# CAA-NMC-OSH_panelized.net
KiCad netlist of a schematic drawn in EAGLE
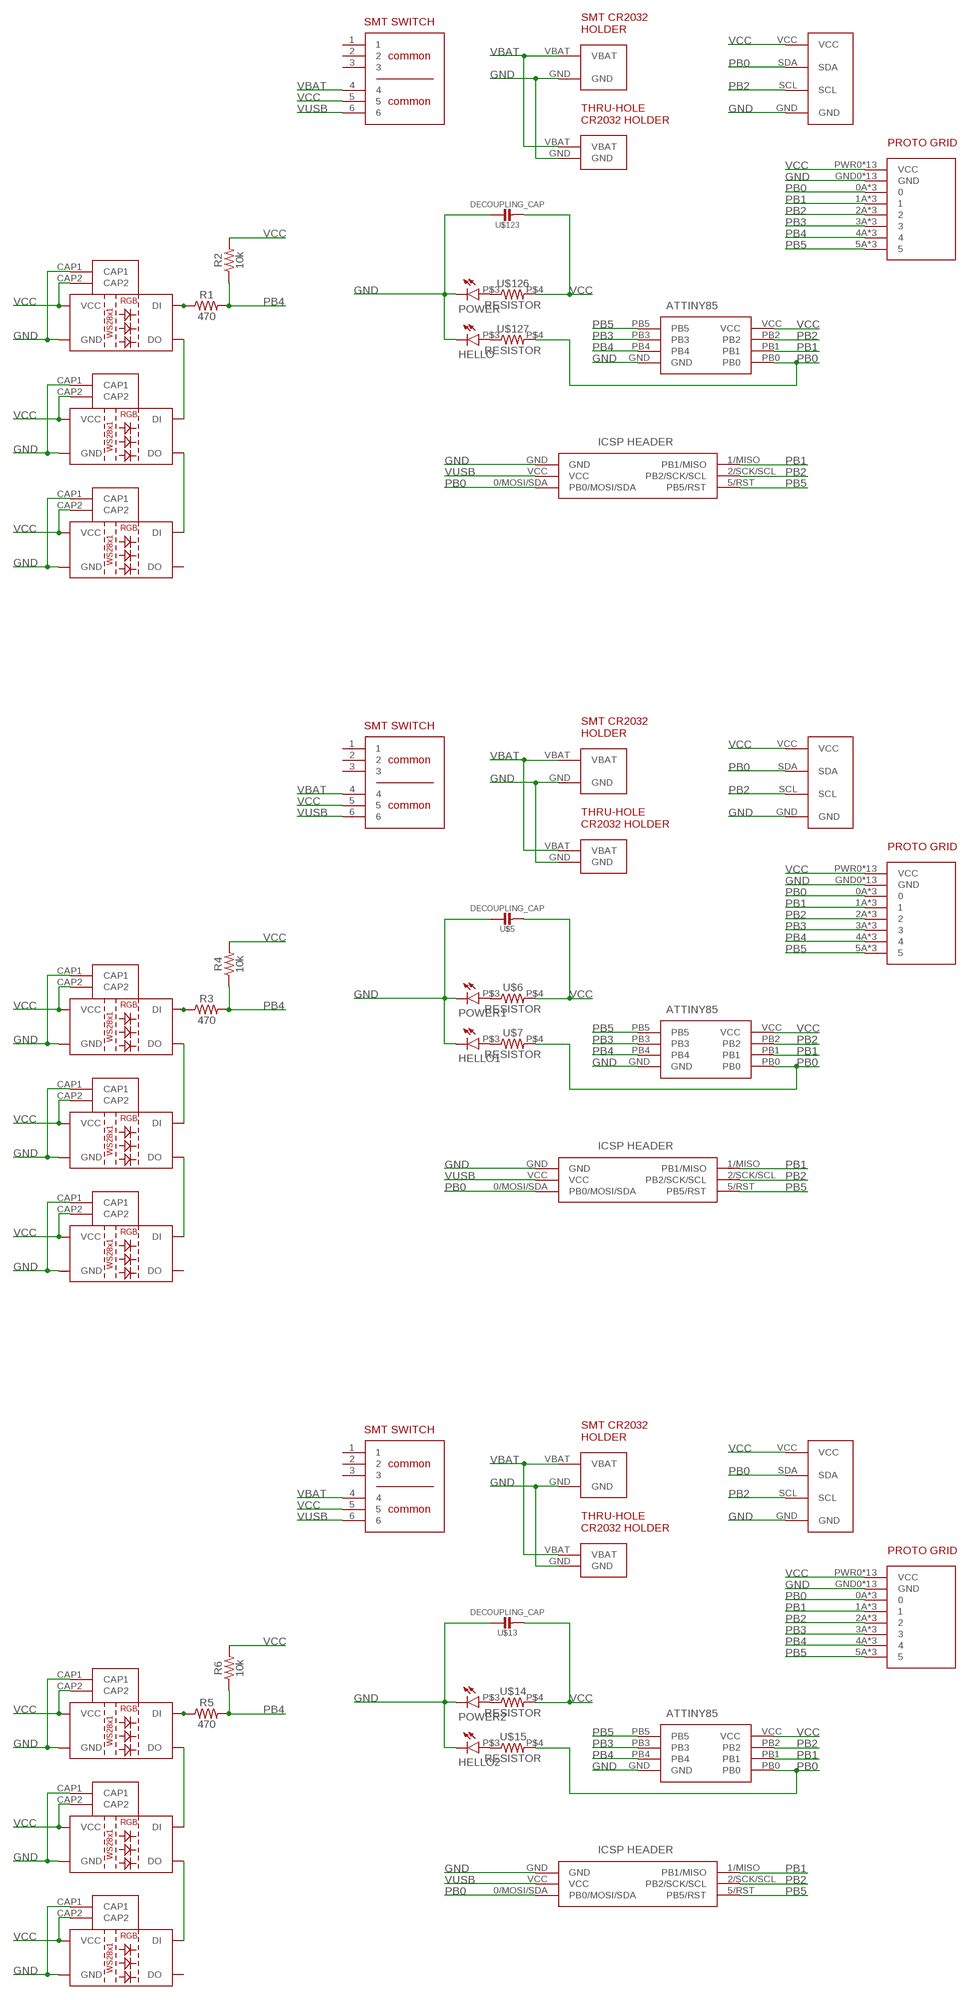
[diagram p0: schematic, sheet 1]

(export (version "E")
  (design (tool "Eeschema 10.0.6"))
  (components
    (comp (ref "D1")
      (value "WS2812B")
      (footprint "eagle-import:WS2812B")
      (libsource (lib "eagle-import") (part "WS2812B"))
    )
    (comp (ref "D2")
      (value "WS2812B")
      (footprint "eagle-import:WS2812B")
      (libsource (lib "eagle-import") (part "WS2812B"))
    )
    (comp (ref "D3")
      (value "WS2812B")
      (footprint "eagle-import:WS2812B")
      (libsource (lib "eagle-import") (part "WS2812B"))
    )
    (comp (ref "D4")
      (value "WS2812B")
      (footprint "eagle-import:WS2812B")
      (libsource (lib "eagle-import") (part "WS2812B"))
    )
    (comp (ref "D5")
      (value "WS2812B")
      (footprint "eagle-import:WS2812B")
      (libsource (lib "eagle-import") (part "WS2812B"))
    )
    (comp (ref "D6")
      (value "WS2812B")
      (footprint "eagle-import:WS2812B")
      (libsource (lib "eagle-import") (part "WS2812B"))
    )
    (comp (ref "D7")
      (value "WS2812B")
      (footprint "eagle-import:WS2812B")
      (libsource (lib "eagle-import") (part "WS2812B"))
    )
    (comp (ref "D8")
      (value "WS2812B")
      (footprint "eagle-import:WS2812B")
      (libsource (lib "eagle-import") (part "WS2812B"))
    )
    (comp (ref "D9")
      (value "WS2812B")
      (footprint "eagle-import:WS2812B")
      (libsource (lib "eagle-import") (part "WS2812B"))
    )
    (comp (ref "HELLO")
      (value "LED3MM")
      (footprint "eagle-import:LED3MM")
      (libsource (lib "eagle-import") (part "LED3MM"))
    )
    (comp (ref "HELLO1")
      (value "LED3MM")
      (footprint "eagle-import:LED3MM")
      (libsource (lib "eagle-import") (part "LED3MM"))
    )
    (comp (ref "HELLO2")
      (value "LED3MM")
      (footprint "eagle-import:LED3MM")
      (libsource (lib "eagle-import") (part "LED3MM"))
    )
    (comp (ref "IC1")
      (value "ATTINY85-20SU")
      (footprint "eagle-import:SOT127P798X216-8N")
      (fields (field (name "RS_PART_NUMBER") "1331674"))
      (libsource (lib "eagle-import") (part "ATTINY85-20SU"))
    )
    (comp (ref "IC2")
      (value "ATTINY85-20SU")
      (footprint "eagle-import:SOT127P798X216-8N")
      (fields (field (name "RS_PART_NUMBER") "1331674"))
      (libsource (lib "eagle-import") (part "ATTINY85-20SU"))
    )
    (comp (ref "IC3")
      (value "ATTINY85-20SU")
      (footprint "eagle-import:SOT127P798X216-8N")
      (fields (field (name "RS_PART_NUMBER") "1331674"))
      (libsource (lib "eagle-import") (part "ATTINY85-20SU"))
    )
    (comp (ref "J1")
      (value "M20-9980346")
      (footprint "eagle-import:HDRV6W64P254_2X3_762X508X868P")
      (fields (field (name "RS_PART_NUMBER") "7457046P"))
      (libsource (lib "eagle-import") (part "M20-9980346"))
    )
    (comp (ref "J2")
      (value "M20-9980346")
      (footprint "eagle-import:HDRV6W64P254_2X3_762X508X868P")
      (fields (field (name "RS_PART_NUMBER") "7457046P"))
      (libsource (lib "eagle-import") (part "M20-9980346"))
    )
    (comp (ref "J3")
      (value "M20-9980346")
      (footprint "eagle-import:HDRV6W64P254_2X3_762X508X868P")
      (fields (field (name "RS_PART_NUMBER") "7457046P"))
      (libsource (lib "eagle-import") (part "M20-9980346"))
    )
    (comp (ref "POWER")
      (value "LED3MM")
      (footprint "eagle-import:LED3MM")
      (libsource (lib "eagle-import") (part "LED3MM"))
    )
    (comp (ref "POWER1")
      (value "LED3MM")
      (footprint "eagle-import:LED3MM")
      (libsource (lib "eagle-import") (part "LED3MM"))
    )
    (comp (ref "POWER2")
      (value "LED3MM")
      (footprint "eagle-import:LED3MM")
      (libsource (lib "eagle-import") (part "LED3MM"))
    )
    (comp (ref "R1")
      (value "470")
      (footprint "eagle-import:0603")
      (libsource (lib "eagle-import") (part "470OHM-0603-1/10W-1%"))
    )
    (comp (ref "R2")
      (value "10k")
      (footprint "eagle-import:0603")
      (libsource (lib "eagle-import") (part "10KOHM-0603-1/10W-1%"))
    )
    (comp (ref "R3")
      (value "470")
      (footprint "eagle-import:0603")
      (libsource (lib "eagle-import") (part "470OHM-0603-1/10W-1%"))
    )
    (comp (ref "R4")
      (value "10k")
      (footprint "eagle-import:0603")
      (libsource (lib "eagle-import") (part "10KOHM-0603-1/10W-1%"))
    )
    (comp (ref "R5")
      (value "470")
      (footprint "eagle-import:0603")
      (libsource (lib "eagle-import") (part "470OHM-0603-1/10W-1%"))
    )
    (comp (ref "R6")
      (value "10k")
      (footprint "eagle-import:0603")
      (libsource (lib "eagle-import") (part "10KOHM-0603-1/10W-1%"))
    )
    (comp (ref "U$1")
      (value "PROTO")
      (footprint "eagle-import:PROTO")
      (libsource (lib "eagle-import") (part "PROTO"))
    )
    (comp (ref "U$2")
      (value "SMT-BATTERY-HOLDER")
      (footprint "eagle-import:SMT-CR-HOLDER")
      (libsource (lib "eagle-import") (part "SMT-BATTERY-HOLDER"))
    )
    (comp (ref "U$3")
      (value "THRU-CR-HOLDER")
      (footprint "eagle-import:THRU-CR-HOLDER")
      (libsource (lib "eagle-import") (part "THRU-CR-HOLDER"))
    )
    (comp (ref "U$4")
      (value "I2C-PADS")
      (footprint "eagle-import:I2C-PADS")
      (libsource (lib "eagle-import") (part "I2C-PADS"))
    )
    (comp (ref "U$5")
      (value "DECOUPLING_CAP")
      (footprint "eagle-import:DECOUPLING_CAP")
      (libsource (lib "eagle-import") (part "DECOUPLING_CAP"))
    )
    (comp (ref "U$6")
      (value "RESISTOR")
      (footprint "eagle-import:AXIAL-0.3")
      (libsource (lib "eagle-import") (part "RESISTOR"))
    )
    (comp (ref "U$7")
      (value "RESISTOR")
      (footprint "eagle-import:AXIAL-0.3")
      (libsource (lib "eagle-import") (part "RESISTOR"))
    )
    (comp (ref "U$8")
      (value "SMT-SWITCH")
      (footprint "eagle-import:SMT-SWITCH")
      (libsource (lib "eagle-import") (part "SMT-SWITCH"))
    )
    (comp (ref "U$9")
      (value "PROTO")
      (footprint "eagle-import:PROTO")
      (libsource (lib "eagle-import") (part "PROTO"))
    )
    (comp (ref "U$10")
      (value "SMT-BATTERY-HOLDER")
      (footprint "eagle-import:SMT-CR-HOLDER")
      (libsource (lib "eagle-import") (part "SMT-BATTERY-HOLDER"))
    )
    (comp (ref "U$11")
      (value "THRU-CR-HOLDER")
      (footprint "eagle-import:THRU-CR-HOLDER")
      (libsource (lib "eagle-import") (part "THRU-CR-HOLDER"))
    )
    (comp (ref "U$12")
      (value "I2C-PADS")
      (footprint "eagle-import:I2C-PADS")
      (libsource (lib "eagle-import") (part "I2C-PADS"))
    )
    (comp (ref "U$13")
      (value "DECOUPLING_CAP")
      (footprint "eagle-import:DECOUPLING_CAP")
      (libsource (lib "eagle-import") (part "DECOUPLING_CAP"))
    )
    (comp (ref "U$14")
      (value "RESISTOR")
      (footprint "eagle-import:AXIAL-0.3")
      (libsource (lib "eagle-import") (part "RESISTOR"))
    )
    (comp (ref "U$15")
      (value "RESISTOR")
      (footprint "eagle-import:AXIAL-0.3")
      (libsource (lib "eagle-import") (part "RESISTOR"))
    )
    (comp (ref "U$16")
      (value "SMT-SWITCH")
      (footprint "eagle-import:SMT-SWITCH")
      (libsource (lib "eagle-import") (part "SMT-SWITCH"))
    )
    (comp (ref "U$17")
      (value "PROTO")
      (footprint "eagle-import:PROTO")
      (libsource (lib "eagle-import") (part "PROTO"))
    )
    (comp (ref "U$18")
      (value "SMT-BATTERY-HOLDER")
      (footprint "eagle-import:SMT-CR-HOLDER")
      (libsource (lib "eagle-import") (part "SMT-BATTERY-HOLDER"))
    )
    (comp (ref "U$19")
      (value "THRU-CR-HOLDER")
      (footprint "eagle-import:THRU-CR-HOLDER")
      (libsource (lib "eagle-import") (part "THRU-CR-HOLDER"))
    )
    (comp (ref "U$20")
      (value "I2C-PADS")
      (footprint "eagle-import:I2C-PADS")
      (libsource (lib "eagle-import") (part "I2C-PADS"))
    )
    (comp (ref "U$123")
      (value "DECOUPLING_CAP")
      (footprint "eagle-import:DECOUPLING_CAP")
      (libsource (lib "eagle-import") (part "DECOUPLING_CAP"))
    )
    (comp (ref "U$126")
      (value "RESISTOR")
      (footprint "eagle-import:AXIAL-0.3")
      (libsource (lib "eagle-import") (part "RESISTOR"))
    )
    (comp (ref "U$127")
      (value "RESISTOR")
      (footprint "eagle-import:AXIAL-0.3")
      (libsource (lib "eagle-import") (part "RESISTOR"))
    )
    (comp (ref "U$145")
      (value "SMT-SWITCH")
      (footprint "eagle-import:SMT-SWITCH")
      (libsource (lib "eagle-import") (part "SMT-SWITCH"))
    )
  )
  (nets
    (net (code "1") (name "/GND") (class "Default")
      (node (ref "D1") (pin "CAP1") (pinfunction "CAP1_CAP1") (pintype "bidirectional"))
      (node (ref "D1") (pin "GND") (pinfunction "GND_GND") (pintype "bidirectional"))
      (node (ref "D2") (pin "CAP1") (pinfunction "CAP1_CAP1") (pintype "bidirectional"))
      (node (ref "D2") (pin "GND") (pinfunction "GND_GND") (pintype "bidirectional"))
      (node (ref "D3") (pin "CAP1") (pinfunction "CAP1_CAP1") (pintype "bidirectional"))
      (node (ref "D3") (pin "GND") (pinfunction "GND_GND") (pintype "bidirectional"))
      (node (ref "D4") (pin "CAP1") (pinfunction "CAP1_CAP1") (pintype "bidirectional"))
      (node (ref "D4") (pin "GND") (pinfunction "GND_GND") (pintype "bidirectional"))
      (node (ref "D5") (pin "CAP1") (pinfunction "CAP1_CAP1") (pintype "bidirectional"))
      (node (ref "D5") (pin "GND") (pinfunction "GND_GND") (pintype "bidirectional"))
      (node (ref "D6") (pin "CAP1") (pinfunction "CAP1_CAP1") (pintype "bidirectional"))
      (node (ref "D6") (pin "GND") (pinfunction "GND_GND") (pintype "bidirectional"))
      (node (ref "D7") (pin "CAP1") (pinfunction "CAP1_CAP1") (pintype "bidirectional"))
      (node (ref "D7") (pin "GND") (pinfunction "GND_GND") (pintype "bidirectional"))
      (node (ref "D8") (pin "CAP1") (pinfunction "CAP1_CAP1") (pintype "bidirectional"))
      (node (ref "D8") (pin "GND") (pinfunction "GND_GND") (pintype "bidirectional"))
      (node (ref "D9") (pin "CAP1") (pinfunction "CAP1_CAP1") (pintype "bidirectional"))
      (node (ref "D9") (pin "GND") (pinfunction "GND_GND") (pintype "bidirectional"))
      (node (ref "HELLO") (pin "NEG") (pinfunction "NEG_NEG") (pintype "passive"))
      (node (ref "HELLO1") (pin "NEG") (pinfunction "NEG_NEG") (pintype "passive"))
      (node (ref "HELLO2") (pin "NEG") (pinfunction "NEG_NEG") (pintype "passive"))
      (node (ref "IC1") (pin "GND") (pinfunction "GND_GND") (pintype "bidirectional"))
      (node (ref "IC2") (pin "GND") (pinfunction "GND_GND") (pintype "bidirectional"))
      (node (ref "IC3") (pin "GND") (pinfunction "GND_GND") (pintype "bidirectional"))
      (node (ref "J1") (pin "GND") (pinfunction "GND_GND") (pintype "bidirectional"))
      (node (ref "J2") (pin "GND") (pinfunction "GND_GND") (pintype "bidirectional"))
      (node (ref "J3") (pin "GND") (pinfunction "GND_GND") (pintype "bidirectional"))
      (node (ref "POWER") (pin "NEG") (pinfunction "NEG_NEG") (pintype "passive"))
      (node (ref "POWER1") (pin "NEG") (pinfunction "NEG_NEG") (pintype "passive"))
      (node (ref "POWER2") (pin "NEG") (pinfunction "NEG_NEG") (pintype "passive"))
      (node (ref "U$1") (pin "GND0") (pinfunction "GND_GND0") (pintype "bidirectional"))
      (node (ref "U$1") (pin "GND1") (pinfunction "GND_GND1") (pintype "bidirectional"))
      (node (ref "U$1") (pin "GND10") (pinfunction "GND_GND10") (pintype "bidirectional"))
      (node (ref "U$1") (pin "GND11") (pinfunction "GND_GND11") (pintype "bidirectional"))
      (node (ref "U$1") (pin "GND12") (pinfunction "GND_GND12") (pintype "bidirectional"))
      (node (ref "U$1") (pin "GND2") (pinfunction "GND_GND2") (pintype "bidirectional"))
      (node (ref "U$1") (pin "GND3") (pinfunction "GND_GND3") (pintype "bidirectional"))
      (node (ref "U$1") (pin "GND4") (pinfunction "GND_GND4") (pintype "bidirectional"))
      (node (ref "U$1") (pin "GND5") (pinfunction "GND_GND5") (pintype "bidirectional"))
      (node (ref "U$1") (pin "GND6") (pinfunction "GND_GND6") (pintype "bidirectional"))
      (node (ref "U$1") (pin "GND7") (pinfunction "GND_GND7") (pintype "bidirectional"))
      (node (ref "U$1") (pin "GND8") (pinfunction "GND_GND8") (pintype "bidirectional"))
      (node (ref "U$1") (pin "GND9") (pinfunction "GND_GND9") (pintype "bidirectional"))
      (node (ref "U$10") (pin "GND") (pinfunction "GND_GND") (pintype "bidirectional"))
      (node (ref "U$11") (pin "GND") (pinfunction "GND_GND") (pintype "bidirectional"))
      (node (ref "U$12") (pin "GND") (pinfunction "GND_GND") (pintype "bidirectional"))
      (node (ref "U$123") (pin "P$1") (pinfunction "1_P$1") (pintype "passive"))
      (node (ref "U$13") (pin "P$1") (pinfunction "1_P$1") (pintype "passive"))
      (node (ref "U$17") (pin "GND0") (pinfunction "GND_GND0") (pintype "bidirectional"))
      (node (ref "U$17") (pin "GND1") (pinfunction "GND_GND1") (pintype "bidirectional"))
      (node (ref "U$17") (pin "GND10") (pinfunction "GND_GND10") (pintype "bidirectional"))
      (node (ref "U$17") (pin "GND11") (pinfunction "GND_GND11") (pintype "bidirectional"))
      (node (ref "U$17") (pin "GND12") (pinfunction "GND_GND12") (pintype "bidirectional"))
      (node (ref "U$17") (pin "GND2") (pinfunction "GND_GND2") (pintype "bidirectional"))
      (node (ref "U$17") (pin "GND3") (pinfunction "GND_GND3") (pintype "bidirectional"))
      (node (ref "U$17") (pin "GND4") (pinfunction "GND_GND4") (pintype "bidirectional"))
      (node (ref "U$17") (pin "GND5") (pinfunction "GND_GND5") (pintype "bidirectional"))
      (node (ref "U$17") (pin "GND6") (pinfunction "GND_GND6") (pintype "bidirectional"))
      (node (ref "U$17") (pin "GND7") (pinfunction "GND_GND7") (pintype "bidirectional"))
      (node (ref "U$17") (pin "GND8") (pinfunction "GND_GND8") (pintype "bidirectional"))
      (node (ref "U$17") (pin "GND9") (pinfunction "GND_GND9") (pintype "bidirectional"))
      (node (ref "U$18") (pin "GND") (pinfunction "GND_GND") (pintype "bidirectional"))
      (node (ref "U$19") (pin "GND") (pinfunction "GND_GND") (pintype "bidirectional"))
      (node (ref "U$2") (pin "GND") (pinfunction "GND_GND") (pintype "bidirectional"))
      (node (ref "U$20") (pin "GND") (pinfunction "GND_GND") (pintype "bidirectional"))
      (node (ref "U$3") (pin "GND") (pinfunction "GND_GND") (pintype "bidirectional"))
      (node (ref "U$4") (pin "GND") (pinfunction "GND_GND") (pintype "bidirectional"))
      (node (ref "U$5") (pin "P$1") (pinfunction "1_P$1") (pintype "passive"))
      (node (ref "U$9") (pin "GND0") (pinfunction "GND_GND0") (pintype "bidirectional"))
      (node (ref "U$9") (pin "GND1") (pinfunction "GND_GND1") (pintype "bidirectional"))
      (node (ref "U$9") (pin "GND10") (pinfunction "GND_GND10") (pintype "bidirectional"))
      (node (ref "U$9") (pin "GND11") (pinfunction "GND_GND11") (pintype "bidirectional"))
      (node (ref "U$9") (pin "GND12") (pinfunction "GND_GND12") (pintype "bidirectional"))
      (node (ref "U$9") (pin "GND2") (pinfunction "GND_GND2") (pintype "bidirectional"))
      (node (ref "U$9") (pin "GND3") (pinfunction "GND_GND3") (pintype "bidirectional"))
      (node (ref "U$9") (pin "GND4") (pinfunction "GND_GND4") (pintype "bidirectional"))
      (node (ref "U$9") (pin "GND5") (pinfunction "GND_GND5") (pintype "bidirectional"))
      (node (ref "U$9") (pin "GND6") (pinfunction "GND_GND6") (pintype "bidirectional"))
      (node (ref "U$9") (pin "GND7") (pinfunction "GND_GND7") (pintype "bidirectional"))
      (node (ref "U$9") (pin "GND8") (pinfunction "GND_GND8") (pintype "bidirectional"))
      (node (ref "U$9") (pin "GND9") (pinfunction "GND_GND9") (pintype "bidirectional"))
    )
    (net (code "2") (name "/PB0") (class "Default")
      (node (ref "IC1") (pin "PB0") (pinfunction "PB0_PB0") (pintype "bidirectional"))
      (node (ref "IC2") (pin "PB0") (pinfunction "PB0_PB0") (pintype "bidirectional"))
      (node (ref "IC3") (pin "PB0") (pinfunction "PB0_PB0") (pintype "bidirectional"))
      (node (ref "J1") (pin "0/MOSI/SDA") (pinfunction "PB0/MOSI/SDA_0/MOSI/SDA") (pintype "bidirectional"))
      (node (ref "J2") (pin "0/MOSI/SDA") (pinfunction "PB0/MOSI/SDA_0/MOSI/SDA") (pintype "bidirectional"))
      (node (ref "J3") (pin "0/MOSI/SDA") (pinfunction "PB0/MOSI/SDA_0/MOSI/SDA") (pintype "bidirectional"))
      (node (ref "U$1") (pin "0A") (pinfunction "0_0A") (pintype "bidirectional"))
      (node (ref "U$1") (pin "0B") (pinfunction "0_0B") (pintype "bidirectional"))
      (node (ref "U$1") (pin "0C") (pinfunction "0_0C") (pintype "bidirectional"))
      (node (ref "U$12") (pin "SDA") (pinfunction "SDA_SDA") (pintype "bidirectional"))
      (node (ref "U$127") (pin "P$4") (pinfunction "2_P$4") (pintype "passive"))
      (node (ref "U$15") (pin "P$4") (pinfunction "2_P$4") (pintype "passive"))
      (node (ref "U$17") (pin "0A") (pinfunction "0_0A") (pintype "bidirectional"))
      (node (ref "U$17") (pin "0B") (pinfunction "0_0B") (pintype "bidirectional"))
      (node (ref "U$17") (pin "0C") (pinfunction "0_0C") (pintype "bidirectional"))
      (node (ref "U$20") (pin "SDA") (pinfunction "SDA_SDA") (pintype "bidirectional"))
      (node (ref "U$4") (pin "SDA") (pinfunction "SDA_SDA") (pintype "bidirectional"))
      (node (ref "U$7") (pin "P$4") (pinfunction "2_P$4") (pintype "passive"))
      (node (ref "U$9") (pin "0A") (pinfunction "0_0A") (pintype "bidirectional"))
      (node (ref "U$9") (pin "0B") (pinfunction "0_0B") (pintype "bidirectional"))
      (node (ref "U$9") (pin "0C") (pinfunction "0_0C") (pintype "bidirectional"))
    )
    (net (code "3") (name "/PB1") (class "Default")
      (node (ref "IC1") (pin "PB1") (pinfunction "PB1_PB1") (pintype "bidirectional"))
      (node (ref "IC2") (pin "PB1") (pinfunction "PB1_PB1") (pintype "bidirectional"))
      (node (ref "IC3") (pin "PB1") (pinfunction "PB1_PB1") (pintype "bidirectional"))
      (node (ref "J1") (pin "1/MISO") (pinfunction "PB1/MISO_1/MISO") (pintype "bidirectional"))
      (node (ref "J2") (pin "1/MISO") (pinfunction "PB1/MISO_1/MISO") (pintype "bidirectional"))
      (node (ref "J3") (pin "1/MISO") (pinfunction "PB1/MISO_1/MISO") (pintype "bidirectional"))
      (node (ref "U$1") (pin "1A") (pinfunction "1_1A") (pintype "bidirectional"))
      (node (ref "U$1") (pin "1B") (pinfunction "1_1B") (pintype "bidirectional"))
      (node (ref "U$1") (pin "1C") (pinfunction "1_1C") (pintype "bidirectional"))
      (node (ref "U$17") (pin "1A") (pinfunction "1_1A") (pintype "bidirectional"))
      (node (ref "U$17") (pin "1B") (pinfunction "1_1B") (pintype "bidirectional"))
      (node (ref "U$17") (pin "1C") (pinfunction "1_1C") (pintype "bidirectional"))
      (node (ref "U$9") (pin "1A") (pinfunction "1_1A") (pintype "bidirectional"))
      (node (ref "U$9") (pin "1B") (pinfunction "1_1B") (pintype "bidirectional"))
      (node (ref "U$9") (pin "1C") (pinfunction "1_1C") (pintype "bidirectional"))
    )
    (net (code "4") (name "/PB2") (class "Default")
      (node (ref "IC1") (pin "PB2") (pinfunction "PB2_PB2") (pintype "bidirectional"))
      (node (ref "IC2") (pin "PB2") (pinfunction "PB2_PB2") (pintype "bidirectional"))
      (node (ref "IC3") (pin "PB2") (pinfunction "PB2_PB2") (pintype "bidirectional"))
      (node (ref "J1") (pin "2/SCK/SCL") (pinfunction "PB2/SCK/SCL_2/SCK/SCL") (pintype "bidirectional"))
      (node (ref "J2") (pin "2/SCK/SCL") (pinfunction "PB2/SCK/SCL_2/SCK/SCL") (pintype "bidirectional"))
      (node (ref "J3") (pin "2/SCK/SCL") (pinfunction "PB2/SCK/SCL_2/SCK/SCL") (pintype "bidirectional"))
      (node (ref "U$1") (pin "2A") (pinfunction "2_2A") (pintype "bidirectional"))
      (node (ref "U$1") (pin "2B") (pinfunction "2_2B") (pintype "bidirectional"))
      (node (ref "U$1") (pin "2C") (pinfunction "2_2C") (pintype "bidirectional"))
      (node (ref "U$12") (pin "SCL") (pinfunction "SCL_SCL") (pintype "bidirectional"))
      (node (ref "U$17") (pin "2A") (pinfunction "2_2A") (pintype "bidirectional"))
      (node (ref "U$17") (pin "2B") (pinfunction "2_2B") (pintype "bidirectional"))
      (node (ref "U$17") (pin "2C") (pinfunction "2_2C") (pintype "bidirectional"))
      (node (ref "U$20") (pin "SCL") (pinfunction "SCL_SCL") (pintype "bidirectional"))
      (node (ref "U$4") (pin "SCL") (pinfunction "SCL_SCL") (pintype "bidirectional"))
      (node (ref "U$9") (pin "2A") (pinfunction "2_2A") (pintype "bidirectional"))
      (node (ref "U$9") (pin "2B") (pinfunction "2_2B") (pintype "bidirectional"))
      (node (ref "U$9") (pin "2C") (pinfunction "2_2C") (pintype "bidirectional"))
    )
    (net (code "5") (name "/PB3") (class "Default")
      (node (ref "IC1") (pin "PB3") (pinfunction "PB3_PB3") (pintype "bidirectional"))
      (node (ref "IC2") (pin "PB3") (pinfunction "PB3_PB3") (pintype "bidirectional"))
      (node (ref "IC3") (pin "PB3") (pinfunction "PB3_PB3") (pintype "bidirectional"))
      (node (ref "U$1") (pin "3A") (pinfunction "3_3A") (pintype "bidirectional"))
      (node (ref "U$1") (pin "3B") (pinfunction "3_3B") (pintype "bidirectional"))
      (node (ref "U$1") (pin "3C") (pinfunction "3_3C") (pintype "bidirectional"))
      (node (ref "U$17") (pin "3A") (pinfunction "3_3A") (pintype "bidirectional"))
      (node (ref "U$17") (pin "3B") (pinfunction "3_3B") (pintype "bidirectional"))
      (node (ref "U$17") (pin "3C") (pinfunction "3_3C") (pintype "bidirectional"))
      (node (ref "U$9") (pin "3A") (pinfunction "3_3A") (pintype "bidirectional"))
      (node (ref "U$9") (pin "3B") (pinfunction "3_3B") (pintype "bidirectional"))
      (node (ref "U$9") (pin "3C") (pinfunction "3_3C") (pintype "bidirectional"))
    )
    (net (code "6") (name "/PB4") (class "Default")
      (node (ref "IC1") (pin "PB4") (pinfunction "PB4_PB4") (pintype "bidirectional"))
      (node (ref "IC2") (pin "PB4") (pinfunction "PB4_PB4") (pintype "bidirectional"))
      (node (ref "IC3") (pin "PB4") (pinfunction "PB4_PB4") (pintype "bidirectional"))
      (node (ref "R1") (pin "2") (pinfunction "2_2") (pintype "passive"))
      (node (ref "R2") (pin "1") (pinfunction "1_1") (pintype "passive"))
      (node (ref "R3") (pin "2") (pinfunction "2_2") (pintype "passive"))
      (node (ref "R4") (pin "1") (pinfunction "1_1") (pintype "passive"))
      (node (ref "R5") (pin "2") (pinfunction "2_2") (pintype "passive"))
      (node (ref "R6") (pin "1") (pinfunction "1_1") (pintype "passive"))
      (node (ref "U$1") (pin "4A") (pinfunction "4_4A") (pintype "bidirectional"))
      (node (ref "U$1") (pin "4B") (pinfunction "4_4B") (pintype "bidirectional"))
      (node (ref "U$1") (pin "4C") (pinfunction "4_4C") (pintype "bidirectional"))
      (node (ref "U$17") (pin "4A") (pinfunction "4_4A") (pintype "bidirectional"))
      (node (ref "U$17") (pin "4B") (pinfunction "4_4B") (pintype "bidirectional"))
      (node (ref "U$17") (pin "4C") (pinfunction "4_4C") (pintype "bidirectional"))
      (node (ref "U$9") (pin "4A") (pinfunction "4_4A") (pintype "bidirectional"))
      (node (ref "U$9") (pin "4B") (pinfunction "4_4B") (pintype "bidirectional"))
      (node (ref "U$9") (pin "4C") (pinfunction "4_4C") (pintype "bidirectional"))
    )
    (net (code "7") (name "/PB5") (class "Default")
      (node (ref "IC1") (pin "PB5") (pinfunction "PB5_PB5") (pintype "bidirectional"))
      (node (ref "IC2") (pin "PB5") (pinfunction "PB5_PB5") (pintype "bidirectional"))
      (node (ref "IC3") (pin "PB5") (pinfunction "PB5_PB5") (pintype "bidirectional"))
      (node (ref "J1") (pin "5/RST") (pinfunction "PB5/RST_5/RST") (pintype "bidirectional"))
      (node (ref "J2") (pin "5/RST") (pinfunction "PB5/RST_5/RST") (pintype "bidirectional"))
      (node (ref "J3") (pin "5/RST") (pinfunction "PB5/RST_5/RST") (pintype "bidirectional"))
      (node (ref "U$1") (pin "5A") (pinfunction "5_5A") (pintype "bidirectional"))
      (node (ref "U$1") (pin "5B") (pinfunction "5_5B") (pintype "bidirectional"))
      (node (ref "U$1") (pin "5C") (pinfunction "5_5C") (pintype "bidirectional"))
      (node (ref "U$17") (pin "5A") (pinfunction "5_5A") (pintype "bidirectional"))
      (node (ref "U$17") (pin "5B") (pinfunction "5_5B") (pintype "bidirectional"))
      (node (ref "U$17") (pin "5C") (pinfunction "5_5C") (pintype "bidirectional"))
      (node (ref "U$9") (pin "5A") (pinfunction "5_5A") (pintype "bidirectional"))
      (node (ref "U$9") (pin "5B") (pinfunction "5_5B") (pintype "bidirectional"))
      (node (ref "U$9") (pin "5C") (pinfunction "5_5C") (pintype "bidirectional"))
    )
    (net (code "8") (name "/VBAT") (class "Default")
      (node (ref "U$10") (pin "VBAT") (pinfunction "VBAT_VBAT") (pintype "bidirectional"))
      (node (ref "U$11") (pin "VBAT") (pinfunction "VBAT_VBAT") (pintype "bidirectional"))
      (node (ref "U$145") (pin "4") (pinfunction "4_4") (pintype "bidirectional"))
      (node (ref "U$16") (pin "4") (pinfunction "4_4") (pintype "bidirectional"))
      (node (ref "U$18") (pin "VBAT") (pinfunction "VBAT_VBAT") (pintype "bidirectional"))
      (node (ref "U$19") (pin "VBAT") (pinfunction "VBAT_VBAT") (pintype "bidirectional"))
      (node (ref "U$2") (pin "VBAT") (pinfunction "VBAT_VBAT") (pintype "bidirectional"))
      (node (ref "U$3") (pin "VBAT") (pinfunction "VBAT_VBAT") (pintype "bidirectional"))
      (node (ref "U$8") (pin "4") (pinfunction "4_4") (pintype "bidirectional"))
    )
    (net (code "9") (name "/VCC") (class "Default")
      (node (ref "D1") (pin "CAP2") (pinfunction "CAP2_CAP2") (pintype "bidirectional"))
      (node (ref "D1") (pin "VCC") (pinfunction "VCC_VCC") (pintype "bidirectional"))
      (node (ref "D2") (pin "CAP2") (pinfunction "CAP2_CAP2") (pintype "bidirectional"))
      (node (ref "D2") (pin "VCC") (pinfunction "VCC_VCC") (pintype "bidirectional"))
      (node (ref "D3") (pin "CAP2") (pinfunction "CAP2_CAP2") (pintype "bidirectional"))
      (node (ref "D3") (pin "VCC") (pinfunction "VCC_VCC") (pintype "bidirectional"))
      (node (ref "D4") (pin "CAP2") (pinfunction "CAP2_CAP2") (pintype "bidirectional"))
      (node (ref "D4") (pin "VCC") (pinfunction "VCC_VCC") (pintype "bidirectional"))
      (node (ref "D5") (pin "CAP2") (pinfunction "CAP2_CAP2") (pintype "bidirectional"))
      (node (ref "D5") (pin "VCC") (pinfunction "VCC_VCC") (pintype "bidirectional"))
      (node (ref "D6") (pin "CAP2") (pinfunction "CAP2_CAP2") (pintype "bidirectional"))
      (node (ref "D6") (pin "VCC") (pinfunction "VCC_VCC") (pintype "bidirectional"))
      (node (ref "D7") (pin "CAP2") (pinfunction "CAP2_CAP2") (pintype "bidirectional"))
      (node (ref "D7") (pin "VCC") (pinfunction "VCC_VCC") (pintype "bidirectional"))
      (node (ref "D8") (pin "CAP2") (pinfunction "CAP2_CAP2") (pintype "bidirectional"))
      (node (ref "D8") (pin "VCC") (pinfunction "VCC_VCC") (pintype "bidirectional"))
      (node (ref "D9") (pin "CAP2") (pinfunction "CAP2_CAP2") (pintype "bidirectional"))
      (node (ref "D9") (pin "VCC") (pinfunction "VCC_VCC") (pintype "bidirectional"))
      (node (ref "IC1") (pin "VCC") (pinfunction "VCC_VCC") (pintype "bidirectional"))
      (node (ref "IC2") (pin "VCC") (pinfunction "VCC_VCC") (pintype "bidirectional"))
      (node (ref "IC3") (pin "VCC") (pinfunction "VCC_VCC") (pintype "bidirectional"))
      (node (ref "R2") (pin "2") (pinfunction "2_2") (pintype "passive"))
      (node (ref "R4") (pin "2") (pinfunction "2_2") (pintype "passive"))
      (node (ref "R6") (pin "2") (pinfunction "2_2") (pintype "passive"))
      (node (ref "U$1") (pin "PWR0") (pinfunction "VCC_PWR0") (pintype "bidirectional"))
      (node (ref "U$1") (pin "PWR1") (pinfunction "VCC_PWR1") (pintype "bidirectional"))
      (node (ref "U$1") (pin "PWR10") (pinfunction "VCC_PWR10") (pintype "bidirectional"))
      (node (ref "U$1") (pin "PWR11") (pinfunction "VCC_PWR11") (pintype "bidirectional"))
      (node (ref "U$1") (pin "PWR12") (pinfunction "VCC_PWR12") (pintype "bidirectional"))
      (node (ref "U$1") (pin "PWR2") (pinfunction "VCC_PWR2") (pintype "bidirectional"))
      (node (ref "U$1") (pin "PWR3") (pinfunction "VCC_PWR3") (pintype "bidirectional"))
      (node (ref "U$1") (pin "PWR4") (pinfunction "VCC_PWR4") (pintype "bidirectional"))
      (node (ref "U$1") (pin "PWR5") (pinfunction "VCC_PWR5") (pintype "bidirectional"))
      (node (ref "U$1") (pin "PWR6") (pinfunction "VCC_PWR6") (pintype "bidirectional"))
      (node (ref "U$1") (pin "PWR7") (pinfunction "VCC_PWR7") (pintype "bidirectional"))
      (node (ref "U$1") (pin "PWR8") (pinfunction "VCC_PWR8") (pintype "bidirectional"))
      (node (ref "U$1") (pin "PWR9") (pinfunction "VCC_PWR9") (pintype "bidirectional"))
      (node (ref "U$12") (pin "VCC") (pinfunction "VCC_VCC") (pintype "bidirectional"))
      (node (ref "U$123") (pin "P$2") (pinfunction "2_P$2") (pintype "passive"))
      (node (ref "U$126") (pin "P$4") (pinfunction "2_P$4") (pintype "passive"))
      (node (ref "U$13") (pin "P$2") (pinfunction "2_P$2") (pintype "passive"))
      (node (ref "U$14") (pin "P$4") (pinfunction "2_P$4") (pintype "passive"))
      (node (ref "U$145") (pin "5") (pinfunction "5_5") (pintype "bidirectional"))
      (node (ref "U$16") (pin "5") (pinfunction "5_5") (pintype "bidirectional"))
      (node (ref "U$17") (pin "PWR0") (pinfunction "VCC_PWR0") (pintype "bidirectional"))
      (node (ref "U$17") (pin "PWR1") (pinfunction "VCC_PWR1") (pintype "bidirectional"))
      (node (ref "U$17") (pin "PWR10") (pinfunction "VCC_PWR10") (pintype "bidirectional"))
      (node (ref "U$17") (pin "PWR11") (pinfunction "VCC_PWR11") (pintype "bidirectional"))
      (node (ref "U$17") (pin "PWR12") (pinfunction "VCC_PWR12") (pintype "bidirectional"))
      (node (ref "U$17") (pin "PWR2") (pinfunction "VCC_PWR2") (pintype "bidirectional"))
      (node (ref "U$17") (pin "PWR3") (pinfunction "VCC_PWR3") (pintype "bidirectional"))
      (node (ref "U$17") (pin "PWR4") (pinfunction "VCC_PWR4") (pintype "bidirectional"))
      (node (ref "U$17") (pin "PWR5") (pinfunction "VCC_PWR5") (pintype "bidirectional"))
      (node (ref "U$17") (pin "PWR6") (pinfunction "VCC_PWR6") (pintype "bidirectional"))
      (node (ref "U$17") (pin "PWR7") (pinfunction "VCC_PWR7") (pintype "bidirectional"))
      (node (ref "U$17") (pin "PWR8") (pinfunction "VCC_PWR8") (pintype "bidirectional"))
      (node (ref "U$17") (pin "PWR9") (pinfunction "VCC_PWR9") (pintype "bidirectional"))
      (node (ref "U$20") (pin "VCC") (pinfunction "VCC_VCC") (pintype "bidirectional"))
      (node (ref "U$4") (pin "VCC") (pinfunction "VCC_VCC") (pintype "bidirectional"))
      (node (ref "U$5") (pin "P$2") (pinfunction "2_P$2") (pintype "passive"))
      (node (ref "U$6") (pin "P$4") (pinfunction "2_P$4") (pintype "passive"))
      (node (ref "U$8") (pin "5") (pinfunction "5_5") (pintype "bidirectional"))
      (node (ref "U$9") (pin "PWR0") (pinfunction "VCC_PWR0") (pintype "bidirectional"))
      (node (ref "U$9") (pin "PWR1") (pinfunction "VCC_PWR1") (pintype "bidirectional"))
      (node (ref "U$9") (pin "PWR10") (pinfunction "VCC_PWR10") (pintype "bidirectional"))
      (node (ref "U$9") (pin "PWR11") (pinfunction "VCC_PWR11") (pintype "bidirectional"))
      (node (ref "U$9") (pin "PWR12") (pinfunction "VCC_PWR12") (pintype "bidirectional"))
      (node (ref "U$9") (pin "PWR2") (pinfunction "VCC_PWR2") (pintype "bidirectional"))
      (node (ref "U$9") (pin "PWR3") (pinfunction "VCC_PWR3") (pintype "bidirectional"))
      (node (ref "U$9") (pin "PWR4") (pinfunction "VCC_PWR4") (pintype "bidirectional"))
      (node (ref "U$9") (pin "PWR5") (pinfunction "VCC_PWR5") (pintype "bidirectional"))
      (node (ref "U$9") (pin "PWR6") (pinfunction "VCC_PWR6") (pintype "bidirectional"))
      (node (ref "U$9") (pin "PWR7") (pinfunction "VCC_PWR7") (pintype "bidirectional"))
      (node (ref "U$9") (pin "PWR8") (pinfunction "VCC_PWR8") (pintype "bidirectional"))
      (node (ref "U$9") (pin "PWR9") (pinfunction "VCC_PWR9") (pintype "bidirectional"))
    )
    (net (code "10") (name "/VUSB") (class "Default")
      (node (ref "J1") (pin "VCC") (pinfunction "VCC_VCC") (pintype "bidirectional"))
      (node (ref "J2") (pin "VCC") (pinfunction "VCC_VCC") (pintype "bidirectional"))
      (node (ref "J3") (pin "VCC") (pinfunction "VCC_VCC") (pintype "bidirectional"))
      (node (ref "U$145") (pin "6") (pinfunction "6_6") (pintype "bidirectional"))
      (node (ref "U$16") (pin "6") (pinfunction "6_6") (pintype "bidirectional"))
      (node (ref "U$8") (pin "6") (pinfunction "6_6") (pintype "bidirectional"))
    )
    (net (code "11") (name "Net-(D1-PadDI)") (class "Default")
      (node (ref "D1") (pin "DI") (pinfunction "DI_DI") (pintype "bidirectional"))
      (node (ref "R1") (pin "1") (pinfunction "1_1") (pintype "passive"))
    )
    (net (code "12") (name "Net-(D1-PadDO)") (class "Default")
      (node (ref "D1") (pin "DO") (pinfunction "DO_DO") (pintype "bidirectional"))
      (node (ref "D2") (pin "DI") (pinfunction "DI_DI") (pintype "bidirectional"))
    )
    (net (code "13") (name "Net-(D2-PadDO)") (class "Default")
      (node (ref "D2") (pin "DO") (pinfunction "DO_DO") (pintype "bidirectional"))
      (node (ref "D3") (pin "DI") (pinfunction "DI_DI") (pintype "bidirectional"))
    )
    (net (code "14") (name "Net-(D4-PadDI)") (class "Default")
      (node (ref "D4") (pin "DI") (pinfunction "DI_DI") (pintype "bidirectional"))
      (node (ref "R3") (pin "1") (pinfunction "1_1") (pintype "passive"))
    )
    (net (code "15") (name "Net-(D4-PadDO)") (class "Default")
      (node (ref "D4") (pin "DO") (pinfunction "DO_DO") (pintype "bidirectional"))
      (node (ref "D5") (pin "DI") (pinfunction "DI_DI") (pintype "bidirectional"))
    )
    (net (code "16") (name "Net-(D5-PadDO)") (class "Default")
      (node (ref "D5") (pin "DO") (pinfunction "DO_DO") (pintype "bidirectional"))
      (node (ref "D6") (pin "DI") (pinfunction "DI_DI") (pintype "bidirectional"))
    )
    (net (code "17") (name "Net-(D7-PadDI)") (class "Default")
      (node (ref "D7") (pin "DI") (pinfunction "DI_DI") (pintype "bidirectional"))
      (node (ref "R5") (pin "1") (pinfunction "1_1") (pintype "passive"))
    )
    (net (code "18") (name "Net-(D7-PadDO)") (class "Default")
      (node (ref "D7") (pin "DO") (pinfunction "DO_DO") (pintype "bidirectional"))
      (node (ref "D8") (pin "DI") (pinfunction "DI_DI") (pintype "bidirectional"))
    )
    (net (code "19") (name "Net-(D8-PadDO)") (class "Default")
      (node (ref "D8") (pin "DO") (pinfunction "DO_DO") (pintype "bidirectional"))
      (node (ref "D9") (pin "DI") (pinfunction "DI_DI") (pintype "bidirectional"))
    )
    (net (code "20") (name "Net-(U$6-1)") (class "Default")
      (node (ref "POWER1") (pin "POS") (pinfunction "POS_POS") (pintype "passive"))
      (node (ref "U$6") (pin "P$3") (pinfunction "1_P$3") (pintype "passive"))
    )
    (net (code "21") (name "Net-(U$7-1)") (class "Default")
      (node (ref "HELLO1") (pin "POS") (pinfunction "POS_POS") (pintype "passive"))
      (node (ref "U$7") (pin "P$3") (pinfunction "1_P$3") (pintype "passive"))
    )
    (net (code "22") (name "Net-(U$14-1)") (class "Default")
      (node (ref "POWER2") (pin "POS") (pinfunction "POS_POS") (pintype "passive"))
      (node (ref "U$14") (pin "P$3") (pinfunction "1_P$3") (pintype "passive"))
    )
    (net (code "23") (name "Net-(U$15-1)") (class "Default")
      (node (ref "HELLO2") (pin "POS") (pinfunction "POS_POS") (pintype "passive"))
      (node (ref "U$15") (pin "P$3") (pinfunction "1_P$3") (pintype "passive"))
    )
    (net (code "24") (name "Net-(U$126-1)") (class "Default")
      (node (ref "POWER") (pin "POS") (pinfunction "POS_POS") (pintype "passive"))
      (node (ref "U$126") (pin "P$3") (pinfunction "1_P$3") (pintype "passive"))
    )
    (net (code "25") (name "Net-(U$127-1)") (class "Default")
      (node (ref "HELLO") (pin "POS") (pinfunction "POS_POS") (pintype "passive"))
      (node (ref "U$127") (pin "P$3") (pinfunction "1_P$3") (pintype "passive"))
    )
    (net (code "26") (name "unconnected-(D3-PadDO)") (class "Default")
      (node (ref "D3") (pin "DO") (pinfunction "DO_DO") (pintype "bidirectional"))
    )
    (net (code "27") (name "unconnected-(D6-PadDO)") (class "Default")
      (node (ref "D6") (pin "DO") (pinfunction "DO_DO") (pintype "bidirectional"))
    )
    (net (code "28") (name "unconnected-(D9-PadDO)") (class "Default")
      (node (ref "D9") (pin "DO") (pinfunction "DO_DO") (pintype "bidirectional"))
    )
    (net (code "29") (name "unconnected-(U$8-Pad1)") (class "Default")
      (node (ref "U$8") (pin "1") (pinfunction "1_1") (pintype "bidirectional"))
    )
    (net (code "30") (name "unconnected-(U$8-Pad2)") (class "Default")
      (node (ref "U$8") (pin "2") (pinfunction "2_2") (pintype "bidirectional"))
    )
    (net (code "31") (name "unconnected-(U$8-Pad3)") (class "Default")
      (node (ref "U$8") (pin "3") (pinfunction "3_3") (pintype "bidirectional"))
    )
    (net (code "32") (name "unconnected-(U$16-Pad1)") (class "Default")
      (node (ref "U$16") (pin "1") (pinfunction "1_1") (pintype "bidirectional"))
    )
    (net (code "33") (name "unconnected-(U$16-Pad2)") (class "Default")
      (node (ref "U$16") (pin "2") (pinfunction "2_2") (pintype "bidirectional"))
    )
    (net (code "34") (name "unconnected-(U$16-Pad3)") (class "Default")
      (node (ref "U$16") (pin "3") (pinfunction "3_3") (pintype "bidirectional"))
    )
    (net (code "35") (name "unconnected-(U$145-Pad1)") (class "Default")
      (node (ref "U$145") (pin "1") (pinfunction "1_1") (pintype "bidirectional"))
    )
    (net (code "36") (name "unconnected-(U$145-Pad2)") (class "Default")
      (node (ref "U$145") (pin "2") (pinfunction "2_2") (pintype "bidirectional"))
    )
    (net (code "37") (name "unconnected-(U$145-Pad3)") (class "Default")
      (node (ref "U$145") (pin "3") (pinfunction "3_3") (pintype "bidirectional"))
    )
  )
)
